# top.net
KiCad netlist of a schematic drawn in Altium Designer
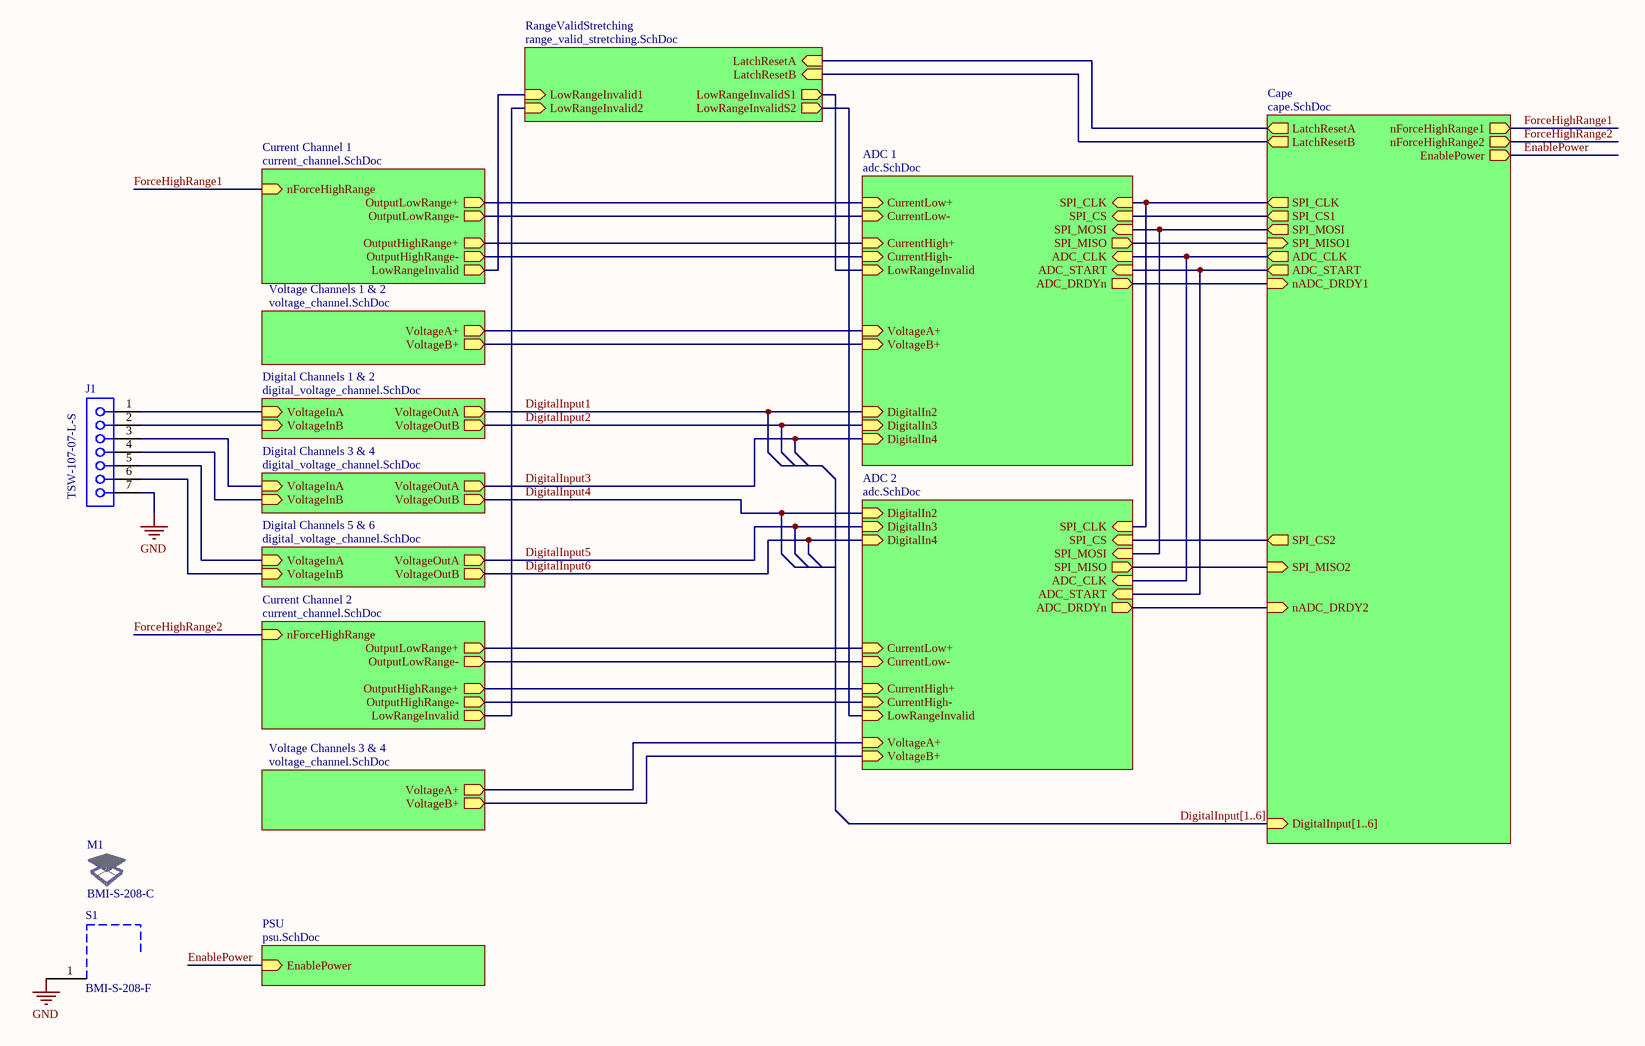
[diagram p0: top.SchDoc]

(export (version "E")
  (design (tool "Eeschema 10.0.6"))
  (components
    (comp (ref "J1")
      (value "TSW-107-07-L-S")
      (footprint "TSW-107-07-L-S")
      (description "Conn Unshrouded Header HDR 7 POS 2.54mm Solder ST Thru-Hole")
      (libsource (lib "TSW-107-07-L-S") (part "TSW-107-07-L-S"))
    )
    (comp (ref "M1")
      (value "BMI-S-208-C")
      (description "Board Mount EMI Enclosures RF Absorber CRS Tin SMD")
      (fields (field (name "MANUFACTURER") "Laird"))
      (libsource (lib "ETHZ Vault") (part "BMI-S-206-C"))
    )
    (comp (ref "S1")
      (value "BMI-S-208-F")
      (footprint "BMI-S-208-F")
      (description "EMI Connector Gaskets & Grounding Pads BLS,2PSH,FRM,SnSat .276x1.559x1.559in")
      (fields (field (name "MANUFACTURER") "Laird Technologies EMI"))
      (libsource (lib "ETHZ Vault") (part "EMI Shield"))
    )
  )
  (nets
    (net (code "39") (name "/VoltageInA") (class "Default")
      (node (ref "J1") (pin "5") (pinfunction "5_5") (pintype "passive"))
    )
    (net (code "40") (name "/VoltageInA_1") (class "Default")
      (node (ref "J1") (pin "1") (pinfunction "1_1") (pintype "passive"))
    )
    (net (code "41") (name "/VoltageInA_2") (class "Default")
      (node (ref "J1") (pin "3") (pinfunction "3_3") (pintype "passive"))
    )
    (net (code "42") (name "/VoltageInB") (class "Default")
      (node (ref "J1") (pin "6") (pinfunction "6_6") (pintype "passive"))
    )
    (net (code "43") (name "/VoltageInB_1") (class "Default")
      (node (ref "J1") (pin "2") (pinfunction "2_2") (pintype "passive"))
    )
    (net (code "44") (name "/VoltageInB_2") (class "Default")
      (node (ref "J1") (pin "4") (pinfunction "4_4") (pintype "passive"))
    )
    (net (code "45") (name "GND") (class "Default")
      (node (ref "J1") (pin "7") (pinfunction "7_7") (pintype "passive"))
      (node (ref "S1") (pin "1") (pintype "passive"))
    )
  )
)
